# MicroView.net
KiCad netlist of a schematic drawn in EAGLE
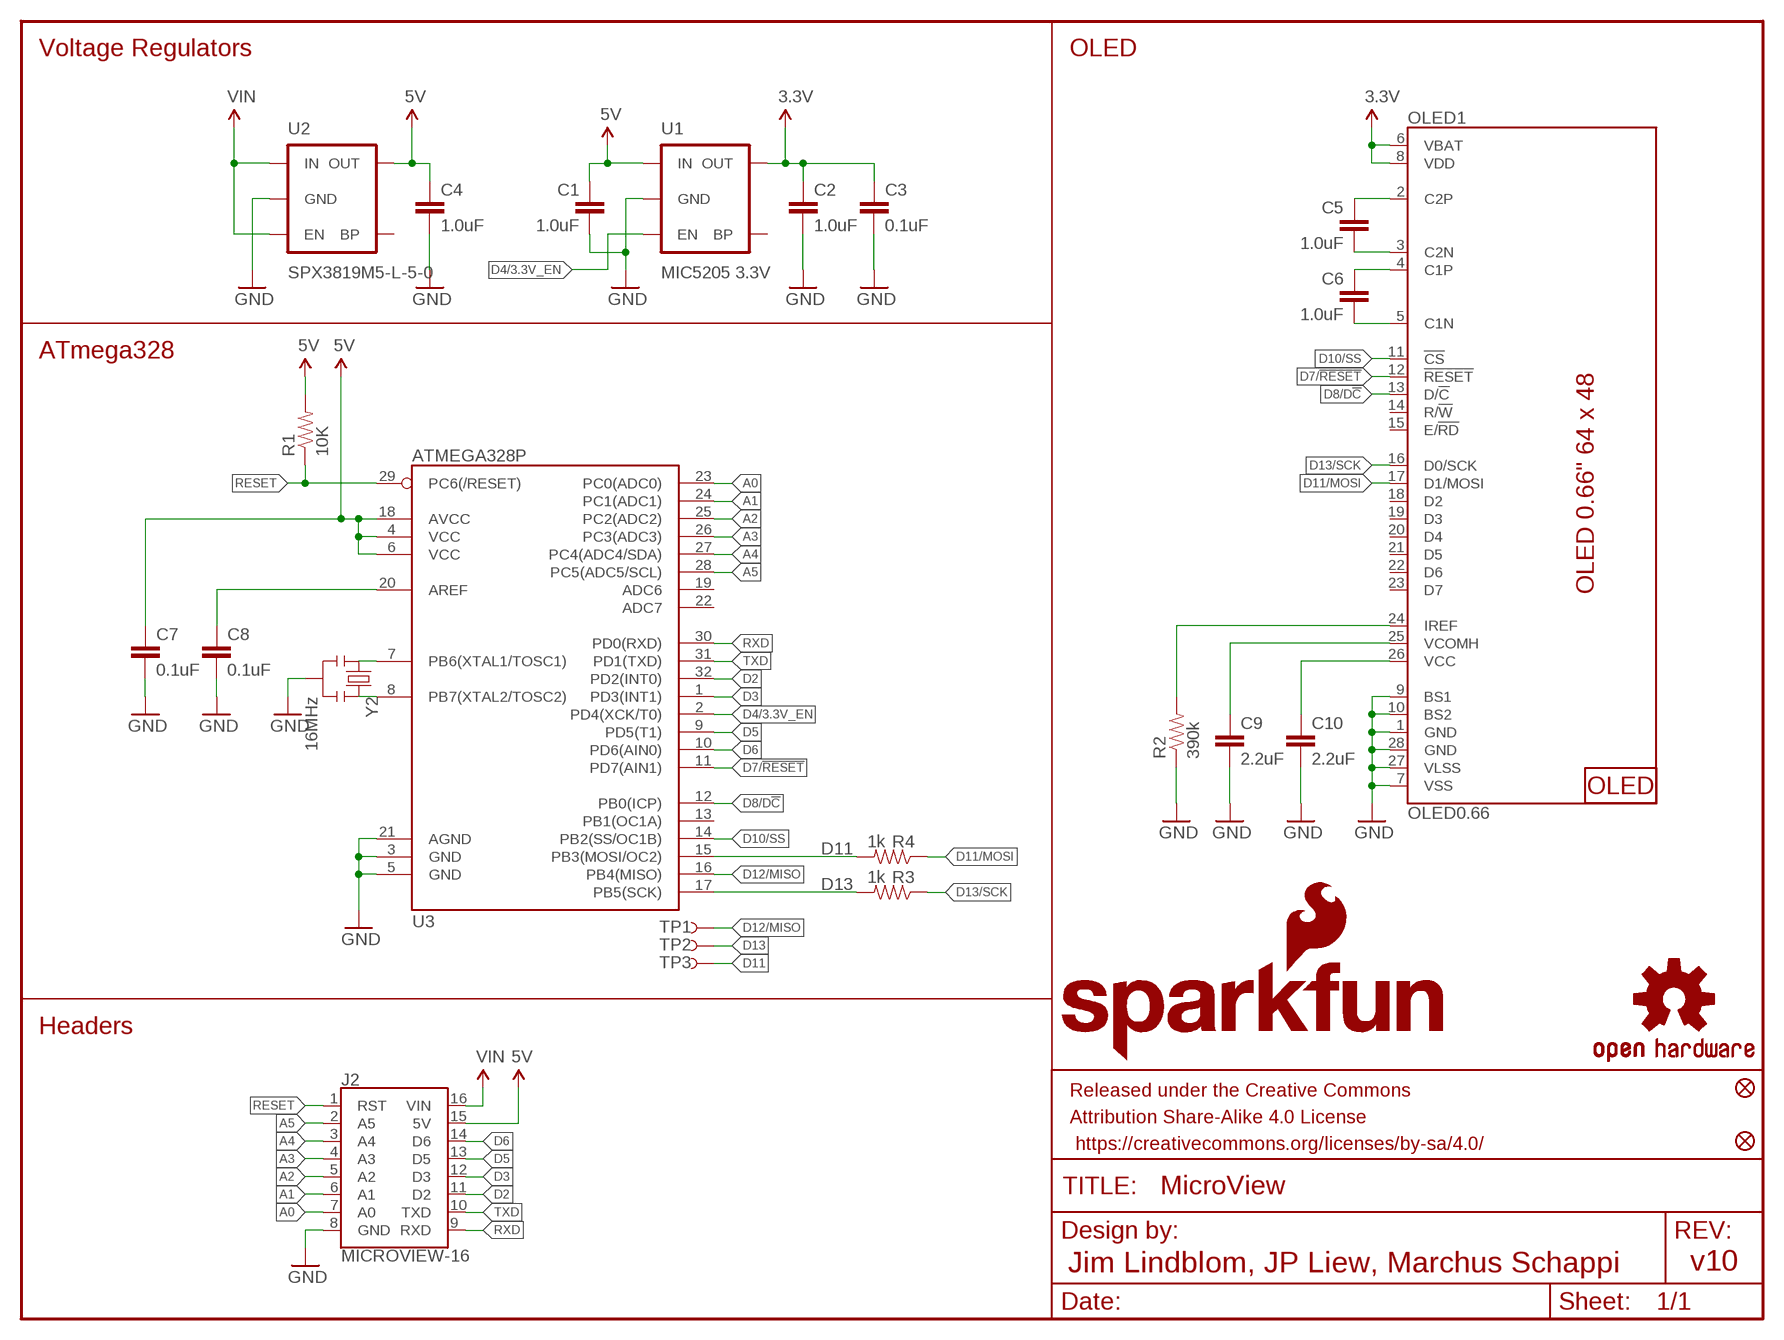
[diagram p0: schematic, sheet 1]

(export (version "E")
  (design (tool "Eeschema 10.0.6"))
  (components
    (comp (ref "C1")
      (value "1.0uF")
      (footprint "eagle-import:0603-CAP")
      (libsource (lib "eagle-import") (part "1.0UF-16V-10%(0603)"))
    )
    (comp (ref "C2")
      (value "1.0uF")
      (footprint "eagle-import:0603-CAP")
      (libsource (lib "eagle-import") (part "1.0UF-16V-10%(0603)"))
    )
    (comp (ref "C3")
      (value "0.1uF")
      (footprint "eagle-import:0603-CAP")
      (libsource (lib "eagle-import") (part "0.1UF-25V(+80/-20%)(0603)"))
    )
    (comp (ref "C4")
      (value "1.0uF")
      (footprint "eagle-import:0603-CAP")
      (libsource (lib "eagle-import") (part "1.0UF-16V-10%(0603)"))
    )
    (comp (ref "C5")
      (value "1.0uF")
      (footprint "eagle-import:0603-CAP")
      (libsource (lib "eagle-import") (part "1.0UF-16V-10%(0603)"))
    )
    (comp (ref "C6")
      (value "1.0uF")
      (footprint "eagle-import:0603-CAP")
      (libsource (lib "eagle-import") (part "1.0UF-16V-10%(0603)"))
    )
    (comp (ref "C7")
      (value "0.1uF")
      (footprint "eagle-import:0603-CAP")
      (libsource (lib "eagle-import") (part "0.1UF-25V(+80/-20%)(0603)"))
    )
    (comp (ref "C8")
      (value "0.1uF")
      (footprint "eagle-import:0603-CAP")
      (libsource (lib "eagle-import") (part "0.1UF-25V(+80/-20%)(0603)"))
    )
    (comp (ref "C9")
      (value "2.2uF")
      (footprint "eagle-import:0603-CAP")
      (libsource (lib "eagle-import") (part "2.2UF-10V-20%(0603)"))
    )
    (comp (ref "C10")
      (value "2.2uF")
      (footprint "eagle-import:0603-CAP")
      (libsource (lib "eagle-import") (part "2.2UF-10V-20%(0603)"))
    )
    (comp (ref "FID1")
      (value "FIDUCIALUFIDUCIAL")
      (footprint "eagle-import:MICRO-FIDUCIAL")
      (libsource (lib "eagle-import") (part "FIDUCIALUFIDUCIAL"))
    )
    (comp (ref "FID3")
      (value "FIDUCIALUFIDUCIAL")
      (footprint "eagle-import:MICRO-FIDUCIAL")
      (libsource (lib "eagle-import") (part "FIDUCIALUFIDUCIAL"))
    )
    (comp (ref "FRAME1")
      (value "FRAME-LETTER")
      (footprint "eagle-import:CREATIVE_COMMONS")
      (libsource (lib "eagle-import") (part "FRAME-LETTER"))
    )
    (comp (ref "J1")
      (value "OLED_SCREEN")
      (footprint "eagle-import:OLED-SCREEN")
      (libsource (lib "eagle-import") (part "OLED_SCREEN"))
    )
    (comp (ref "J2")
      (value "MICROVIEW-16")
      (footprint "eagle-import:MV-DIP16")
      (libsource (lib "eagle-import") (part "MICROVIEW-16"))
    )
    (comp (ref "LOGO1")
      (value "OSHW-LOGOS")
      (footprint "eagle-import:OSHW-LOGO-S")
      (libsource (lib "eagle-import") (part "OSHW-LOGOS"))
    )
    (comp (ref "LOGO4")
      (value "SFE_LOGO_NAME_FLAME.1_INCH")
      (footprint "eagle-import:SFE_LOGO_NAME_FLAME_.1")
      (libsource (lib "eagle-import") (part "SFE_LOGO_NAME_FLAME.1_INCH"))
    )
    (comp (ref "OLED1")
      (value "OLED0.66")
      (footprint "eagle-import:OLED-0.66-64X48")
      (libsource (lib "eagle-import") (part "OLED0.66"))
    )
    (comp (ref "R1")
      (value "10K")
      (footprint "eagle-import:0603-RES")
      (libsource (lib "eagle-import") (part "10KOHM1/10W1%(0603)0603"))
    )
    (comp (ref "R2")
      (value "390k")
      (footprint "eagle-import:0603-RES")
      (libsource (lib "eagle-import") (part "RESISTOR0603"))
    )
    (comp (ref "R3")
      (value "1k")
      (footprint "eagle-import:0603-RES")
      (libsource (lib "eagle-import") (part "10KOHM1/10W1%(0603)0603"))
    )
    (comp (ref "R4")
      (value "1k")
      (footprint "eagle-import:0603-RES")
      (libsource (lib "eagle-import") (part "10KOHM1/10W1%(0603)0603"))
    )
    (comp (ref "TP1")
      (value "TEST-POINT3X5")
      (footprint "eagle-import:PAD.03X.05")
      (libsource (lib "eagle-import") (part "TEST-POINT3X5"))
    )
    (comp (ref "TP2")
      (value "TEST-POINT3X5")
      (footprint "eagle-import:PAD.03X.05")
      (libsource (lib "eagle-import") (part "TEST-POINT3X5"))
    )
    (comp (ref "TP3")
      (value "TEST-POINT3X5")
      (footprint "eagle-import:PAD.03X.05")
      (libsource (lib "eagle-import") (part "TEST-POINT3X5"))
    )
    (comp (ref "U1")
      (value "MIC5205 3.3V")
      (footprint "eagle-import:SOT23-5")
      (libsource (lib "eagle-import") (part "V_REG_MIC52053.3V"))
    )
    (comp (ref "U2")
      (value "SPX3819M5-L-5-0")
      (footprint "eagle-import:SOT23-5")
      (libsource (lib "eagle-import") (part "V_REG_MIC52195V"))
    )
    (comp (ref "U3")
      (value "ATMEGA328P")
      (footprint "eagle-import:TQFP32-08")
      (libsource (lib "eagle-import") (part "ATMEGA328_SMT"))
    )
    (comp (ref "Y2")
      (value "16MHz")
      (footprint "eagle-import:RESONATOR-SMD")
      (libsource (lib "eagle-import") (part "RESONATORSMD"))
    )
  )
  (nets
    (net (code "1") (name "/D7{slash}~{RESET}") (class "Default")
      (node (ref "OLED1") (pin "12") (pinfunction "~{RESET}_12") (pintype "bidirectional"))
      (node (ref "U3") (pin "11") (pinfunction "PD7(AIN1)_11") (pintype "bidirectional"))
    )
    (net (code "2") (name "/D8{slash}D~{C}") (class "Default")
      (node (ref "OLED1") (pin "13") (pinfunction "D/~{C}_13") (pintype "bidirectional"))
      (node (ref "U3") (pin "12") (pinfunction "PB0(ICP)_12") (pintype "bidirectional"))
    )
    (net (code "3") (name "3.3V") (class "Default")
      (node (ref "C2") (pin "1") (pinfunction "1_1") (pintype "passive"))
      (node (ref "C3") (pin "1") (pinfunction "1_1") (pintype "passive"))
      (node (ref "OLED1") (pin "6") (pinfunction "VBAT_6") (pintype "bidirectional"))
      (node (ref "OLED1") (pin "8") (pinfunction "VDD_8") (pintype "bidirectional"))
      (node (ref "U1") (pin "5") (pinfunction "OUT_5") (pintype "passive"))
    )
    (net (code "4") (name "5V") (class "Default")
      (node (ref "C1") (pin "1") (pinfunction "1_1") (pintype "passive"))
      (node (ref "C4") (pin "1") (pinfunction "1_1") (pintype "passive"))
      (node (ref "C7") (pin "1") (pinfunction "1_1") (pintype "passive"))
      (node (ref "J2") (pin "15") (pinfunction "5V_15") (pintype "output"))
      (node (ref "R1") (pin "2") (pinfunction "2_2") (pintype "passive"))
      (node (ref "U1") (pin "1") (pinfunction "IN_1") (pintype "input"))
      (node (ref "U2") (pin "5") (pinfunction "OUT_5") (pintype "passive"))
      (node (ref "U3") (pin "18") (pinfunction "AVCC_18") (pintype "bidirectional"))
      (node (ref "U3") (pin "4") (pinfunction "VCC_4") (pintype "bidirectional"))
      (node (ref "U3") (pin "6") (pinfunction "VCC_6") (pintype "bidirectional"))
    )
    (net (code "5") (name "A0") (class "Default")
      (node (ref "J2") (pin "7") (pinfunction "A0_7") (pintype "output"))
      (node (ref "U3") (pin "23") (pinfunction "PC0(ADC0)_23") (pintype "bidirectional"))
    )
    (net (code "6") (name "A1") (class "Default")
      (node (ref "J2") (pin "6") (pinfunction "A1_6") (pintype "output"))
      (node (ref "U3") (pin "24") (pinfunction "PC1(ADC1)_24") (pintype "bidirectional"))
    )
    (net (code "7") (name "A2") (class "Default")
      (node (ref "J2") (pin "5") (pinfunction "A2_5") (pintype "output"))
      (node (ref "U3") (pin "25") (pinfunction "PC2(ADC2)_25") (pintype "bidirectional"))
    )
    (net (code "8") (name "A3") (class "Default")
      (node (ref "J2") (pin "4") (pinfunction "A3_4") (pintype "output"))
      (node (ref "U3") (pin "26") (pinfunction "PC3(ADC3)_26") (pintype "bidirectional"))
    )
    (net (code "9") (name "A4") (class "Default")
      (node (ref "J2") (pin "3") (pinfunction "A4_3") (pintype "output"))
      (node (ref "U3") (pin "27") (pinfunction "PC4(ADC4/SDA)_27") (pintype "bidirectional"))
    )
    (net (code "10") (name "A5") (class "Default")
      (node (ref "J2") (pin "2") (pinfunction "A5_2") (pintype "output"))
      (node (ref "U3") (pin "28") (pinfunction "PC5(ADC5/SCL)_28") (pintype "bidirectional"))
    )
    (net (code "11") (name "D2") (class "Default")
      (node (ref "J2") (pin "11") (pinfunction "D2_11") (pintype "output"))
      (node (ref "U3") (pin "32") (pinfunction "PD2(INT0)_32") (pintype "bidirectional"))
    )
    (net (code "12") (name "D3") (class "Default")
      (node (ref "J2") (pin "12") (pinfunction "D3_12") (pintype "output"))
      (node (ref "U3") (pin "1") (pinfunction "PD3(INT1)_1") (pintype "bidirectional"))
    )
    (net (code "13") (name "D4{slash}3.3V_EN") (class "Default")
      (node (ref "U1") (pin "3") (pinfunction "EN_3") (pintype "input"))
      (node (ref "U3") (pin "2") (pinfunction "PD4(XCK/T0)_2") (pintype "bidirectional"))
    )
    (net (code "14") (name "D5") (class "Default")
      (node (ref "J2") (pin "13") (pinfunction "D5_13") (pintype "output"))
      (node (ref "U3") (pin "9") (pinfunction "PD5(T1)_9") (pintype "bidirectional"))
    )
    (net (code "15") (name "D6") (class "Default")
      (node (ref "J2") (pin "14") (pinfunction "D6_14") (pintype "output"))
      (node (ref "U3") (pin "10") (pinfunction "PD6(AIN0)_10") (pintype "bidirectional"))
    )
    (net (code "16") (name "D10{slash}SS") (class "Default")
      (node (ref "OLED1") (pin "11") (pinfunction "~{CS}_11") (pintype "bidirectional"))
      (node (ref "U3") (pin "14") (pinfunction "PB2(SS/OC1B)_14") (pintype "bidirectional"))
    )
    (net (code "17") (name "D11") (class "Default")
      (node (ref "R4") (pin "2") (pinfunction "2_2") (pintype "passive"))
      (node (ref "TP3") (pin "P$1") (pinfunction "1_P$1") (pintype "bidirectional"))
      (node (ref "U3") (pin "15") (pinfunction "PB3(MOSI/OC2)_15") (pintype "bidirectional"))
    )
    (net (code "18") (name "D11{slash}MOSI") (class "Default")
      (node (ref "OLED1") (pin "17") (pinfunction "D1/MOSI_17") (pintype "bidirectional"))
      (node (ref "R4") (pin "1") (pinfunction "1_1") (pintype "passive"))
    )
    (net (code "19") (name "D12{slash}MISO") (class "Default")
      (node (ref "TP1") (pin "P$1") (pinfunction "1_P$1") (pintype "bidirectional"))
      (node (ref "U3") (pin "16") (pinfunction "PB4(MISO)_16") (pintype "bidirectional"))
    )
    (net (code "20") (name "D13") (class "Default")
      (node (ref "R3") (pin "2") (pinfunction "2_2") (pintype "passive"))
      (node (ref "TP2") (pin "P$1") (pinfunction "1_P$1") (pintype "bidirectional"))
      (node (ref "U3") (pin "17") (pinfunction "PB5(SCK)_17") (pintype "bidirectional"))
    )
    (net (code "21") (name "D13{slash}SCK") (class "Default")
      (node (ref "OLED1") (pin "16") (pinfunction "D0/SCK_16") (pintype "bidirectional"))
      (node (ref "R3") (pin "1") (pinfunction "1_1") (pintype "passive"))
    )
    (net (code "22") (name "GND") (class "Default")
      (node (ref "C1") (pin "2") (pinfunction "2_2") (pintype "passive"))
      (node (ref "C10") (pin "2") (pinfunction "2_2") (pintype "passive"))
      (node (ref "C2") (pin "2") (pinfunction "2_2") (pintype "passive"))
      (node (ref "C3") (pin "2") (pinfunction "2_2") (pintype "passive"))
      (node (ref "C4") (pin "2") (pinfunction "2_2") (pintype "passive"))
      (node (ref "C7") (pin "2") (pinfunction "2_2") (pintype "passive"))
      (node (ref "C8") (pin "2") (pinfunction "2_2") (pintype "passive"))
      (node (ref "C9") (pin "2") (pinfunction "2_2") (pintype "passive"))
      (node (ref "J2") (pin "8") (pinfunction "GND_8") (pintype "output"))
      (node (ref "OLED1") (pin "1") (pinfunction "GND_1") (pintype "bidirectional"))
      (node (ref "OLED1") (pin "10") (pinfunction "BS2_10") (pintype "bidirectional"))
      (node (ref "OLED1") (pin "27") (pinfunction "VLSS_27") (pintype "bidirectional"))
      (node (ref "OLED1") (pin "28") (pinfunction "GND_28") (pintype "bidirectional"))
      (node (ref "OLED1") (pin "7") (pinfunction "VSS_7") (pintype "bidirectional"))
      (node (ref "OLED1") (pin "9") (pinfunction "BS1_9") (pintype "bidirectional"))
      (node (ref "R2") (pin "1") (pinfunction "1_1") (pintype "passive"))
      (node (ref "U1") (pin "2") (pinfunction "GND_2") (pintype "input"))
      (node (ref "U2") (pin "2") (pinfunction "GND_2") (pintype "input"))
      (node (ref "U3") (pin "21") (pinfunction "AGND_21") (pintype "bidirectional"))
      (node (ref "U3") (pin "3") (pinfunction "GND_3") (pintype "bidirectional"))
      (node (ref "U3") (pin "5") (pinfunction "GND_5") (pintype "bidirectional"))
      (node (ref "Y2") (pin "2") (pinfunction "2_2") (pintype "passive"))
    )
    (net (code "23") (name "Net-(OLED1-C1N)") (class "Default")
      (node (ref "C6") (pin "2") (pinfunction "2_2") (pintype "passive"))
      (node (ref "OLED1") (pin "5") (pinfunction "C1N_5") (pintype "bidirectional"))
    )
    (net (code "24") (name "Net-(OLED1-C1P)") (class "Default")
      (node (ref "C6") (pin "1") (pinfunction "1_1") (pintype "passive"))
      (node (ref "OLED1") (pin "4") (pinfunction "C1P_4") (pintype "bidirectional"))
    )
    (net (code "25") (name "Net-(OLED1-C2N)") (class "Default")
      (node (ref "C5") (pin "2") (pinfunction "2_2") (pintype "passive"))
      (node (ref "OLED1") (pin "3") (pinfunction "C2N_3") (pintype "bidirectional"))
    )
    (net (code "26") (name "Net-(OLED1-C2P)") (class "Default")
      (node (ref "C5") (pin "1") (pinfunction "1_1") (pintype "passive"))
      (node (ref "OLED1") (pin "2") (pinfunction "C2P_2") (pintype "bidirectional"))
    )
    (net (code "27") (name "Net-(OLED1-IREF)") (class "Default")
      (node (ref "OLED1") (pin "24") (pinfunction "IREF_24") (pintype "bidirectional"))
      (node (ref "R2") (pin "2") (pinfunction "2_2") (pintype "passive"))
    )
    (net (code "28") (name "Net-(OLED1-VCC)") (class "Default")
      (node (ref "C10") (pin "1") (pinfunction "1_1") (pintype "passive"))
      (node (ref "OLED1") (pin "26") (pinfunction "VCC_26") (pintype "bidirectional"))
    )
    (net (code "29") (name "Net-(OLED1-VCOMH)") (class "Default")
      (node (ref "C9") (pin "1") (pinfunction "1_1") (pintype "passive"))
      (node (ref "OLED1") (pin "25") (pinfunction "VCOMH_25") (pintype "bidirectional"))
    )
    (net (code "30") (name "Net-(U3-AREF)") (class "Default")
      (node (ref "C8") (pin "1") (pinfunction "1_1") (pintype "passive"))
      (node (ref "U3") (pin "20") (pinfunction "AREF_20") (pintype "bidirectional"))
    )
    (net (code "31") (name "Net-(U3-PB6(XTAL1{slash}TOSC1))") (class "Default")
      (node (ref "U3") (pin "7") (pinfunction "PB6(XTAL1/TOSC1)_7") (pintype "bidirectional"))
      (node (ref "Y2") (pin "1") (pinfunction "1_1") (pintype "passive"))
    )
    (net (code "32") (name "Net-(U3-PB7(XTAL2{slash}TOSC2))") (class "Default")
      (node (ref "U3") (pin "8") (pinfunction "PB7(XTAL2/TOSC2)_8") (pintype "bidirectional"))
      (node (ref "Y2") (pin "3") (pinfunction "3_3") (pintype "passive"))
    )
    (net (code "33") (name "RESET") (class "Default")
      (node (ref "J2") (pin "1") (pinfunction "RST_1") (pintype "output"))
      (node (ref "R1") (pin "1") (pinfunction "1_1") (pintype "passive"))
      (node (ref "U3") (pin "29") (pinfunction "PC6(/RESET)_29") (pintype "bidirectional"))
    )
    (net (code "34") (name "RXD") (class "Default")
      (node (ref "J2") (pin "9") (pinfunction "RXD_9") (pintype "output"))
      (node (ref "U3") (pin "30") (pinfunction "PD0(RXD)_30") (pintype "bidirectional"))
    )
    (net (code "35") (name "TXD") (class "Default")
      (node (ref "J2") (pin "10") (pinfunction "TXD_10") (pintype "output"))
      (node (ref "U3") (pin "31") (pinfunction "PD1(TXD)_31") (pintype "bidirectional"))
    )
    (net (code "36") (name "VIN") (class "Default")
      (node (ref "J2") (pin "16") (pinfunction "VIN_16") (pintype "output"))
      (node (ref "U2") (pin "1") (pinfunction "IN_1") (pintype "input"))
      (node (ref "U2") (pin "3") (pinfunction "EN_3") (pintype "input"))
    )
    (net (code "37") (name "unconnected-(OLED1-D2-Pad18)") (class "Default")
      (node (ref "OLED1") (pin "18") (pinfunction "D2_18") (pintype "bidirectional"))
    )
    (net (code "38") (name "unconnected-(OLED1-D3-Pad19)") (class "Default")
      (node (ref "OLED1") (pin "19") (pinfunction "D3_19") (pintype "bidirectional"))
    )
    (net (code "39") (name "unconnected-(OLED1-D4-Pad20)") (class "Default")
      (node (ref "OLED1") (pin "20") (pinfunction "D4_20") (pintype "bidirectional"))
    )
    (net (code "40") (name "unconnected-(OLED1-D5-Pad21)") (class "Default")
      (node (ref "OLED1") (pin "21") (pinfunction "D5_21") (pintype "bidirectional"))
    )
    (net (code "41") (name "unconnected-(OLED1-D6-Pad22)") (class "Default")
      (node (ref "OLED1") (pin "22") (pinfunction "D6_22") (pintype "bidirectional"))
    )
    (net (code "42") (name "unconnected-(OLED1-D7-Pad23)") (class "Default")
      (node (ref "OLED1") (pin "23") (pinfunction "D7_23") (pintype "bidirectional"))
    )
    (net (code "43") (name "unconnected-(OLED1-E{slash}~{RD}-Pad15)") (class "Default")
      (node (ref "OLED1") (pin "15") (pinfunction "E/~{RD}_15") (pintype "bidirectional"))
    )
    (net (code "44") (name "unconnected-(OLED1-R{slash}~{W}-Pad14)") (class "Default")
      (node (ref "OLED1") (pin "14") (pinfunction "R/~{W}_14") (pintype "bidirectional"))
    )
    (net (code "45") (name "unconnected-(U1-BP-Pad4)") (class "Default")
      (node (ref "U1") (pin "4") (pinfunction "BP_4") (pintype "input"))
    )
    (net (code "46") (name "unconnected-(U2-BP-Pad4)") (class "Default")
      (node (ref "U2") (pin "4") (pinfunction "BP_4") (pintype "input"))
    )
    (net (code "47") (name "unconnected-(U3-ADC6-Pad19)") (class "Default")
      (node (ref "U3") (pin "19") (pinfunction "ADC6_19") (pintype "bidirectional"))
    )
    (net (code "48") (name "unconnected-(U3-ADC7-Pad22)") (class "Default")
      (node (ref "U3") (pin "22") (pinfunction "ADC7_22") (pintype "bidirectional"))
    )
    (net (code "49") (name "unconnected-(U3-PB1(OC1A)-Pad13)") (class "Default")
      (node (ref "U3") (pin "13") (pinfunction "PB1(OC1A)_13") (pintype "bidirectional"))
    )
  )
)
